# buck_12-3v3_mcc.net
KiCad netlist of a schematic drawn in EAGLE
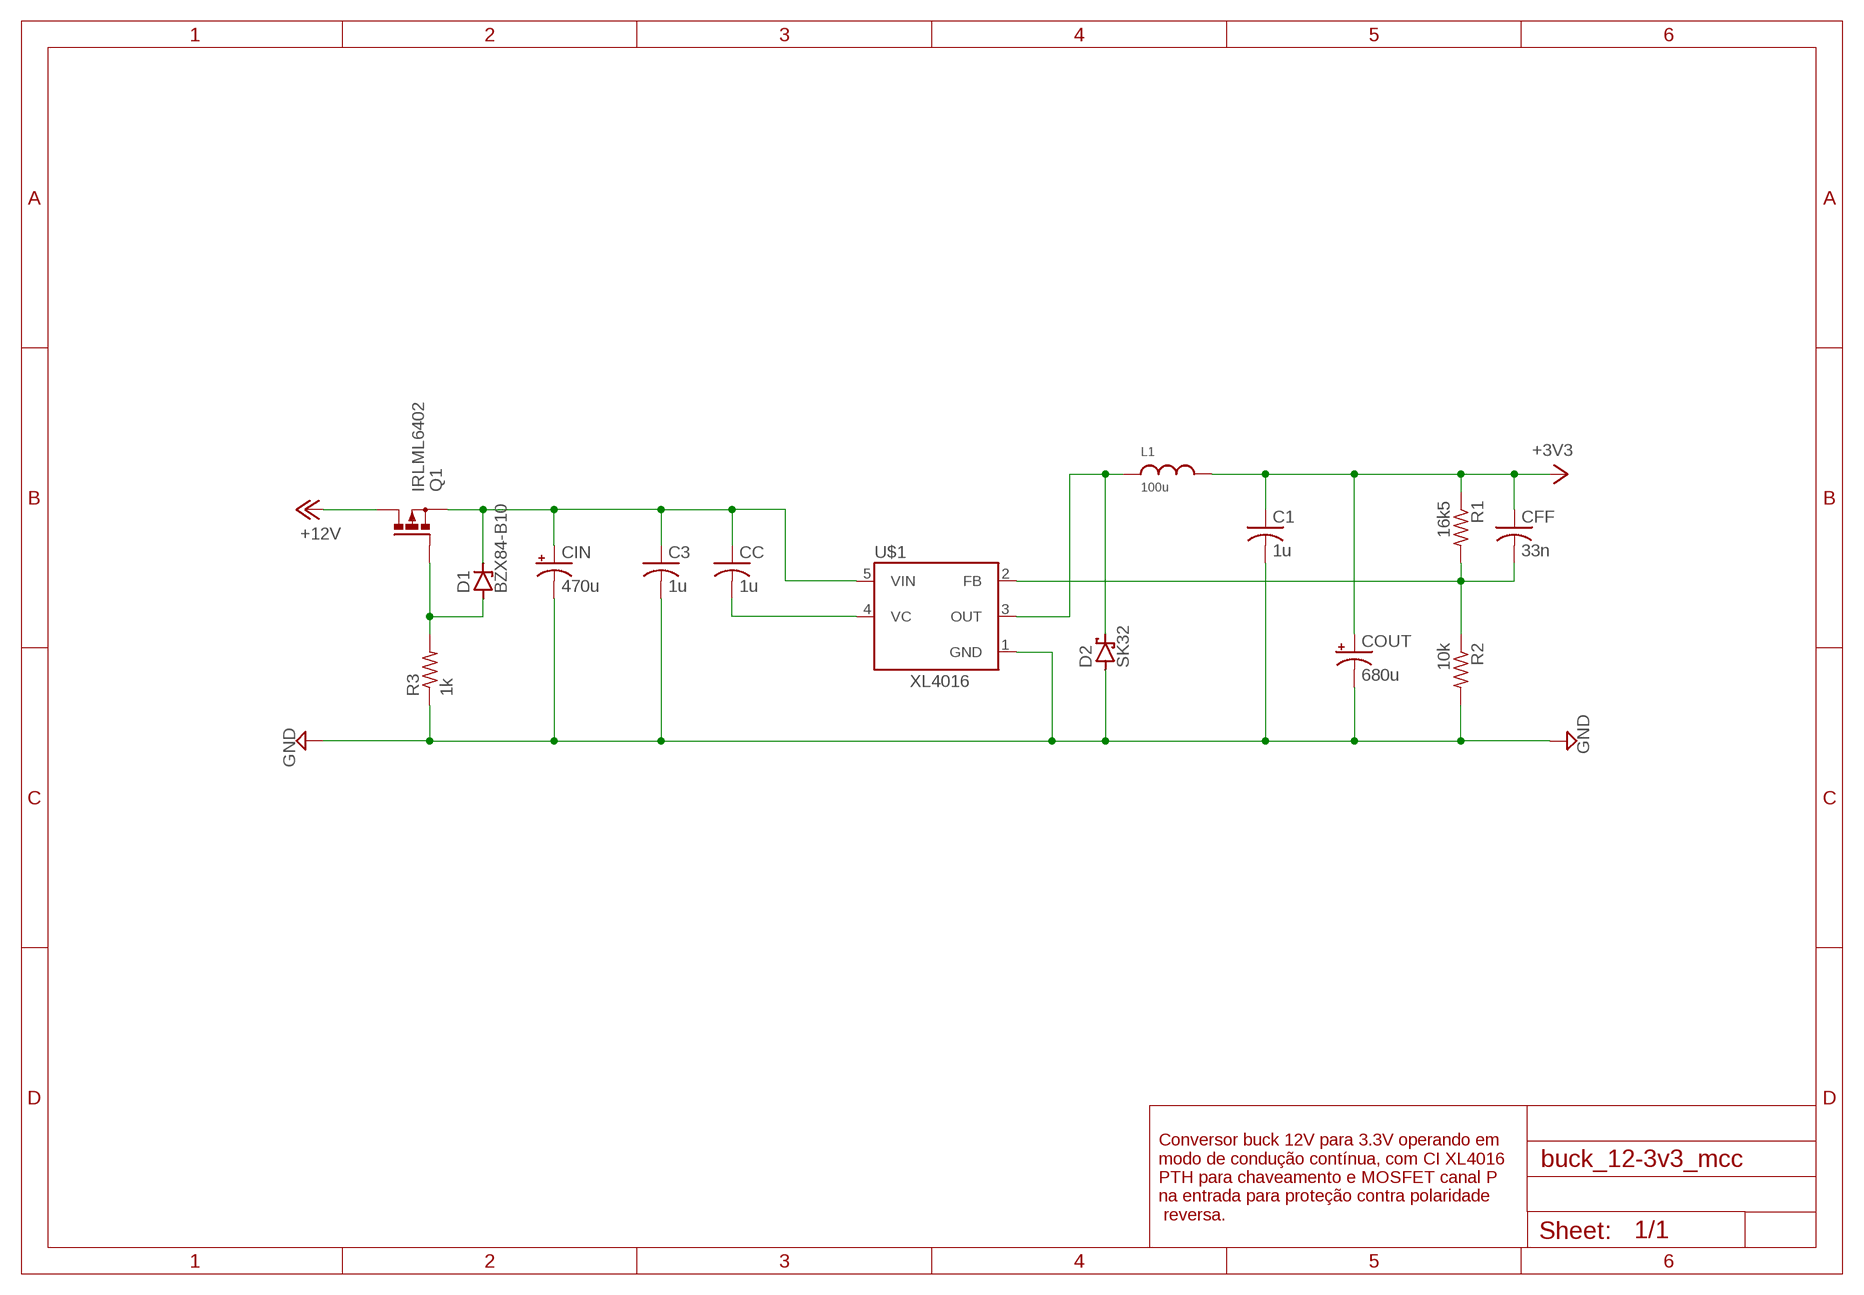
[diagram p0: schematic, sheet 1]

(export (version "E")
  (design (tool "Eeschema 10.0.6"))
  (components
    (comp (ref "C1")
      (value "1u")
      (footprint "eagle-import:C1206")
      (libsource (lib "eagle-import") (part "C-USC1206"))
    )
    (comp (ref "C3")
      (value "1u")
      (footprint "eagle-import:C1206")
      (libsource (lib "eagle-import") (part "C-USC1206"))
    )
    (comp (ref "CC")
      (value "1u")
      (footprint "eagle-import:C1206")
      (libsource (lib "eagle-import") (part "C-USC1206"))
    )
    (comp (ref "CFF")
      (value "33n")
      (footprint "eagle-import:C1206")
      (libsource (lib "eagle-import") (part "C-USC1206"))
    )
    (comp (ref "CIN")
      (value "470u")
      (footprint "eagle-import:E3,5-8")
      (libsource (lib "eagle-import") (part "CPOL-USE3.5-8"))
    )
    (comp (ref "COUT")
      (value "680u")
      (footprint "eagle-import:E3,5-8")
      (libsource (lib "eagle-import") (part "CPOL-USE3.5-8"))
    )
    (comp (ref "D1")
      (value "BZX84-B10")
      (footprint "eagle-import:SOT23")
      (libsource (lib "eagle-import") (part "ZENER-DIODESOT23"))
    )
    (comp (ref "D2")
      (value "SK32")
      (footprint "eagle-import:SMC")
      (libsource (lib "eagle-import") (part "SCHOTTKY-DIODESMC"))
    )
    (comp (ref "L1")
      (value "100u")
      (footprint "eagle-import:INDUTOR_125125")
      (libsource (lib "eagle-import") (part "INDUCTOR_125125"))
    )
    (comp (ref "Q1")
      (value "IRLML6402")
      (footprint "eagle-import:SOT-23")
      (libsource (lib "eagle-import") (part "IRLML6402"))
    )
    (comp (ref "R1")
      (value "16k5")
      (footprint "eagle-import:R1206")
      (libsource (lib "eagle-import") (part "R-US_R1206"))
    )
    (comp (ref "R2")
      (value "10k")
      (footprint "eagle-import:R1206")
      (libsource (lib "eagle-import") (part "R-US_R1206"))
    )
    (comp (ref "R3")
      (value "1k")
      (footprint "eagle-import:M1206")
      (libsource (lib "eagle-import") (part "R-US_M1206"))
    )
    (comp (ref "U$1")
      (value "XL4016")
      (footprint "eagle-import:LM2576T2")
      (fields (field (name "MF") "XLSEMI"))
      (libsource (lib "eagle-import") (part "XL4016"))
    )
  )
  (nets
    (net (code "1") (name "+3V3") (class "Default")
      (node (ref "C1") (pin "1") (pinfunction "1_1") (pintype "passive"))
      (node (ref "CFF") (pin "1") (pinfunction "1_1") (pintype "passive"))
      (node (ref "COUT") (pin "+") (pinfunction "+_+") (pintype "passive"))
      (node (ref "L1") (pin "P$2") (pinfunction "P$2_P$2") (pintype "bidirectional"))
      (node (ref "R1") (pin "1") (pinfunction "1_1") (pintype "passive"))
    )
    (net (code "2") (name "+12V") (class "Default")
      (node (ref "Q1") (pin "P3") (pinfunction "D_P3") (pintype "passive"))
    )
    (net (code "3") (name "GND") (class "Default")
      (node (ref "C1") (pin "2") (pinfunction "2_2") (pintype "passive"))
      (node (ref "C3") (pin "2") (pinfunction "2_2") (pintype "passive"))
      (node (ref "CIN") (pin "-") (pinfunction "-_-") (pintype "passive"))
      (node (ref "COUT") (pin "-") (pinfunction "-_-") (pintype "passive"))
      (node (ref "D2") (pin "A") (pinfunction "A_A") (pintype "passive"))
      (node (ref "R2") (pin "2") (pinfunction "2_2") (pintype "passive"))
      (node (ref "R3") (pin "1") (pinfunction "1_1") (pintype "passive"))
      (node (ref "U$1") (pin "1") (pinfunction "GND_1") (pintype "power_in"))
    )
    (net (code "4") (name "Net-(D1-A)") (class "Default")
      (node (ref "D1") (pin "1") (pinfunction "A_1") (pintype "passive"))
      (node (ref "Q1") (pin "P1") (pinfunction "G_P1") (pintype "passive"))
      (node (ref "R3") (pin "2") (pinfunction "2_2") (pintype "passive"))
    )
    (net (code "5") (name "Net-(D1-C)") (class "Default")
      (node (ref "C3") (pin "1") (pinfunction "1_1") (pintype "passive"))
      (node (ref "CC") (pin "1") (pinfunction "1_1") (pintype "passive"))
      (node (ref "CIN") (pin "+") (pinfunction "+_+") (pintype "passive"))
      (node (ref "D1") (pin "3") (pinfunction "C_3") (pintype "passive"))
      (node (ref "Q1") (pin "P2") (pinfunction "S_P2") (pintype "passive"))
      (node (ref "U$1") (pin "5") (pinfunction "VIN_5") (pintype "power_in"))
    )
    (net (code "6") (name "Net-(U$1-FB)") (class "Default")
      (node (ref "CFF") (pin "2") (pinfunction "2_2") (pintype "passive"))
      (node (ref "R1") (pin "2") (pinfunction "2_2") (pintype "passive"))
      (node (ref "R2") (pin "1") (pinfunction "1_1") (pintype "passive"))
      (node (ref "U$1") (pin "2") (pinfunction "FB_2") (pintype "input"))
    )
    (net (code "7") (name "Net-(U$1-OUT)") (class "Default")
      (node (ref "D2") (pin "C") (pinfunction "C_C") (pintype "passive"))
      (node (ref "L1") (pin "P$1") (pinfunction "P$1_P$1") (pintype "bidirectional"))
      (node (ref "U$1") (pin "3") (pinfunction "OUT_3") (pintype "output"))
    )
    (net (code "8") (name "Net-(U$1-VC)") (class "Default")
      (node (ref "CC") (pin "2") (pinfunction "2_2") (pintype "passive"))
      (node (ref "U$1") (pin "4") (pinfunction "VC_4") (pintype "input"))
    )
  )
)
